# ADC_CLK.net
KiCad netlist of a schematic drawn in Altium Designer
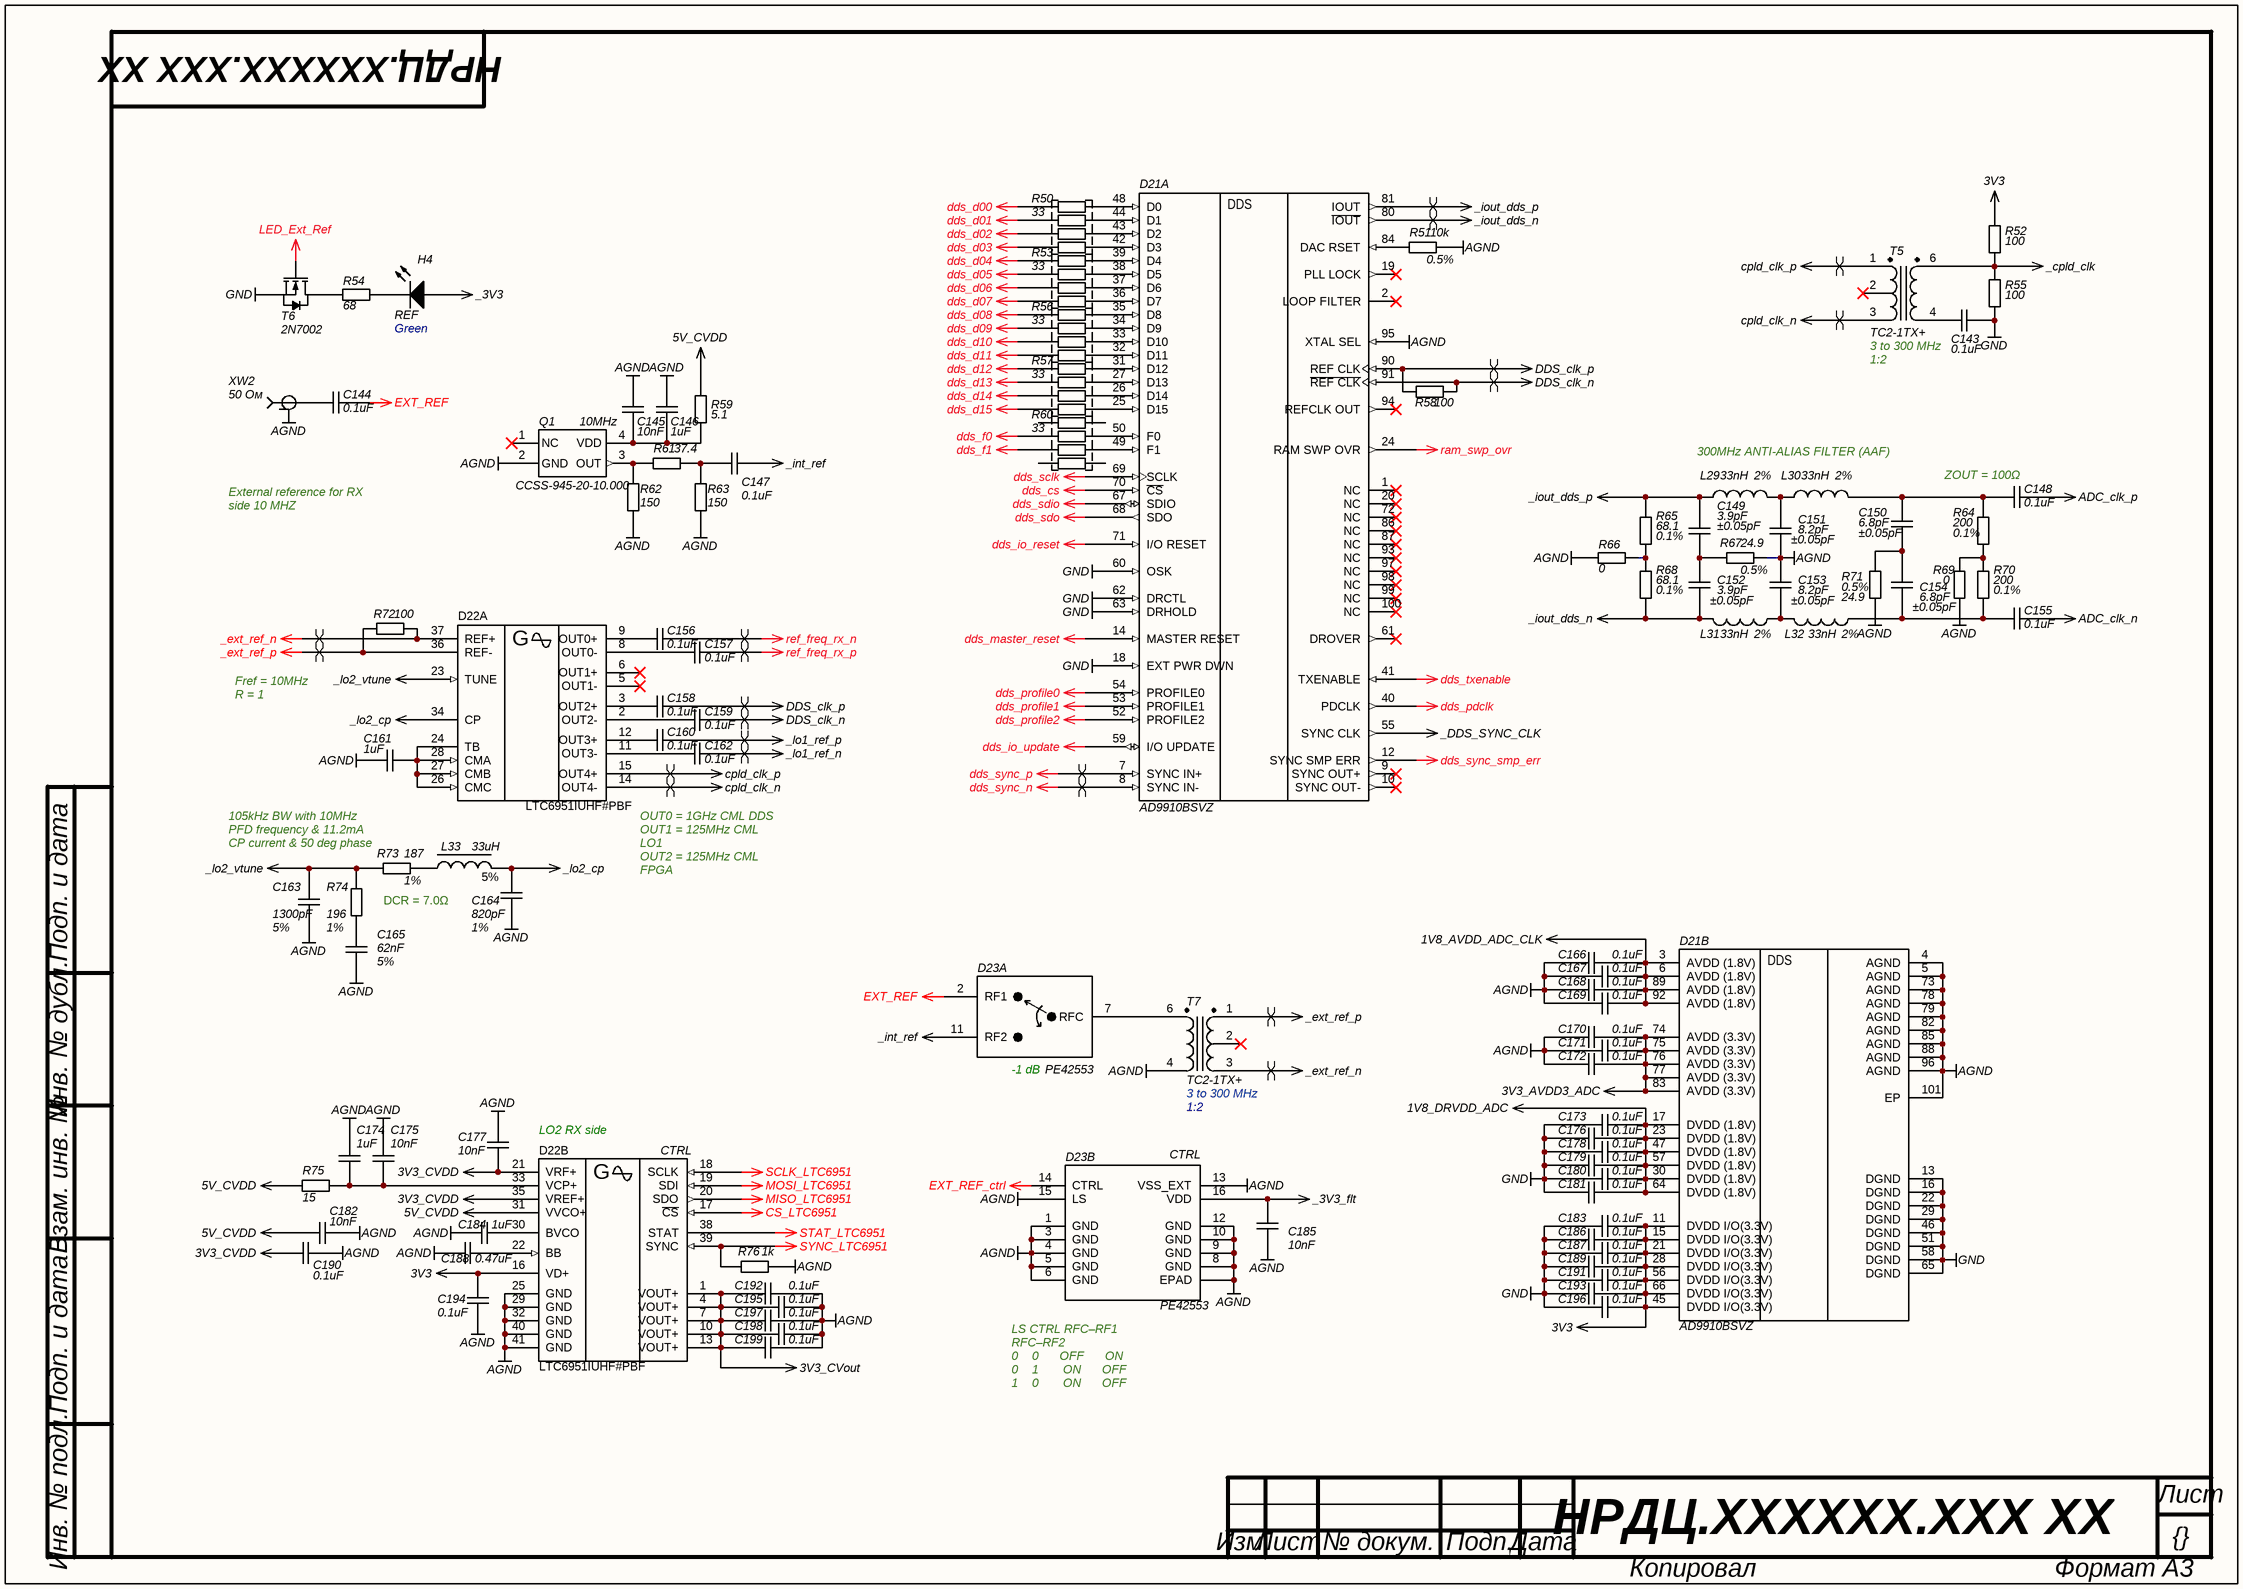
[diagram p0: ADC_CLK.SchDoc]

(export (version "E")
  (design (tool "Eeschema 10.0.6"))
  (components
    (comp (ref "C143")
      (value "0.1uF")
      (footprint "C0402")
      (description "SMD Capacitor")
      (fields (field (name "MANUFACTURER") "Murata") (field (name "TOLERANCE") "10%"))
      (libsource (lib "Kintex_SDR") (part "CAP"))
    )
    (comp (ref "C144")
      (value "0.1uF")
      (footprint "C0402")
      (description "SMD Capacitor")
      (fields (field (name "MANUFACTURER") "Murata") (field (name "TOLERANCE") "10%"))
      (libsource (lib "Kintex_SDR") (part "CAP"))
    )
    (comp (ref "C145")
      (value "10nF")
      (footprint "C0402")
      (description "SMD Capacitor")
      (fields (field (name "MANUFACTURER") "Murata") (field (name "TOLERANCE") "10%"))
      (libsource (lib "Kintex_SDR") (part "CAP"))
    )
    (comp (ref "C146")
      (value "1uF")
      (footprint "C0805")
      (description "SMD Capacitor")
      (fields (field (name "MANUFACTURER") "Murata") (field (name "TOLERANCE") "10%"))
      (libsource (lib "Kintex_SDR") (part "CAP"))
    )
    (comp (ref "C147")
      (value "0.1uF")
      (footprint "C0402")
      (description "SMD Capacitor")
      (fields (field (name "MANUFACTURER") "Murata") (field (name "TOLERANCE") "10%"))
      (libsource (lib "Kintex_SDR") (part "CAP"))
    )
    (comp (ref "C148")
      (value "0.1uF")
      (footprint "C0402")
      (description "SMD Capacitor")
      (fields (field (name "MANUFACTURER") "Murata") (field (name "TOLERANCE") "10%"))
      (libsource (lib "Kintex_SDR") (part "CAP"))
    )
    (comp (ref "C149")
      (value "3.9pF")
      (footprint "C0402")
      (description "SMD Capacitor")
      (fields
        (field (name "MANUFACTURER") "Murata")
        (field (name "TOLERANCE") "±0.05pF")
        (field (name "VOLTAGE") "50V")
      )
      (libsource (lib "Kintex_SDR") (part "CAP"))
    )
    (comp (ref "C150")
      (value "6.8pF")
      (footprint "C0402")
      (description "SMD Capacitor")
      (fields
        (field (name "MANUFACTURER") "Murata")
        (field (name "TOLERANCE") "±0.05pF")
        (field (name "VOLTAGE") "50V")
      )
      (libsource (lib "Kintex_SDR") (part "CAP"))
    )
    (comp (ref "C151")
      (value "8.2pF")
      (footprint "C0402")
      (description "SMD Capacitor")
      (fields
        (field (name "MANUFACTURER") "Murata")
        (field (name "TOLERANCE") "±0.05pF")
        (field (name "VOLTAGE") "50V")
      )
      (libsource (lib "Kintex_SDR") (part "CAP"))
    )
    (comp (ref "C152")
      (value "3.9pF")
      (footprint "C0402")
      (description "SMD Capacitor")
      (fields
        (field (name "MANUFACTURER") "Murata")
        (field (name "TOLERANCE") "±0.05pF")
        (field (name "VOLTAGE") "50V")
      )
      (libsource (lib "Kintex_SDR") (part "CAP"))
    )
    (comp (ref "C153")
      (value "8.2pF")
      (footprint "C0402")
      (description "SMD Capacitor")
      (fields
        (field (name "MANUFACTURER") "Murata")
        (field (name "TOLERANCE") "±0.05pF")
        (field (name "VOLTAGE") "50V")
      )
      (libsource (lib "Kintex_SDR") (part "CAP"))
    )
    (comp (ref "C154")
      (value "6.8pF")
      (footprint "C0402")
      (description "SMD Capacitor")
      (fields
        (field (name "MANUFACTURER") "Murata")
        (field (name "TOLERANCE") "±0.05pF")
        (field (name "VOLTAGE") "50V")
      )
      (libsource (lib "Kintex_SDR") (part "CAP"))
    )
    (comp (ref "C155")
      (value "0.1uF")
      (footprint "C0402")
      (description "SMD Capacitor")
      (fields (field (name "MANUFACTURER") "Murata") (field (name "TOLERANCE") "10%"))
      (libsource (lib "Kintex_SDR") (part "CAP"))
    )
    (comp (ref "C156")
      (value "0.1uF")
      (footprint "C0402")
      (description "SMD Capacitor")
      (fields (field (name "MANUFACTURER") "Murata") (field (name "TOLERANCE") "10%"))
      (libsource (lib "Kintex_SDR") (part "CAP"))
    )
    (comp (ref "C157")
      (value "0.1uF")
      (footprint "C0402")
      (description "SMD Capacitor")
      (fields (field (name "MANUFACTURER") "Murata") (field (name "TOLERANCE") "10%"))
      (libsource (lib "Kintex_SDR") (part "CAP"))
    )
    (comp (ref "C158")
      (value "0.1uF")
      (footprint "C0402")
      (description "SMD Capacitor")
      (fields (field (name "MANUFACTURER") "Murata") (field (name "TOLERANCE") "10%"))
      (libsource (lib "Kintex_SDR") (part "CAP"))
    )
    (comp (ref "C159")
      (value "0.1uF")
      (footprint "C0402")
      (description "SMD Capacitor")
      (fields (field (name "MANUFACTURER") "Murata") (field (name "TOLERANCE") "10%"))
      (libsource (lib "Kintex_SDR") (part "CAP"))
    )
    (comp (ref "C160")
      (value "0.1uF")
      (footprint "C0402")
      (description "SMD Capacitor")
      (fields (field (name "MANUFACTURER") "Murata") (field (name "TOLERANCE") "10%"))
      (libsource (lib "Kintex_SDR") (part "CAP"))
    )
    (comp (ref "C161")
      (value "1uF")
      (footprint "C0402")
      (description "SMD Capacitor")
      (fields (field (name "MANUFACTURER") "Murata") (field (name "TOLERANCE") "10%"))
      (libsource (lib "Kintex_SDR") (part "CAP"))
    )
    (comp (ref "C162")
      (value "0.1uF")
      (footprint "C0402")
      (description "SMD Capacitor")
      (fields (field (name "MANUFACTURER") "Murata") (field (name "TOLERANCE") "10%"))
      (libsource (lib "Kintex_SDR") (part "CAP"))
    )
    (comp (ref "C163")
      (value "1300pF")
      (footprint "C0603")
      (description "SMD Capacitor")
      (fields
        (field (name "MANUFACTURER") "Murata")
        (field (name "TOLERANCE") "5%")
        (field (name "VOLTAGE") "50V")
      )
      (libsource (lib "Kintex_SDR") (part "CAP"))
    )
    (comp (ref "C164")
      (value "820pF")
      (footprint "C0603")
      (description "SMD Capacitor")
      (fields
        (field (name "MANUFACTURER") "Murata")
        (field (name "TOLERANCE") "1%")
        (field (name "VOLTAGE") "100V")
      )
      (libsource (lib "Kintex_SDR") (part "CAP"))
    )
    (comp (ref "C165")
      (value "62nF")
      (footprint "C1206")
      (description "SMD Capacitor")
      (fields
        (field (name "MANUFACTURER") "Murata")
        (field (name "TOLERANCE") "5%")
        (field (name "VOLTAGE") "50V")
      )
      (libsource (lib "Kintex_SDR") (part "CAP"))
    )
    (comp (ref "C166")
      (value "0.1uF")
      (footprint "C0402")
      (description "SMD Capacitor")
      (fields (field (name "MANUFACTURER") "Murata") (field (name "TOLERANCE") "10%"))
      (libsource (lib "Kintex_SDR") (part "CAP"))
    )
    (comp (ref "C167")
      (value "0.1uF")
      (footprint "C0402")
      (description "SMD Capacitor")
      (fields (field (name "MANUFACTURER") "Murata") (field (name "TOLERANCE") "10%"))
      (libsource (lib "Kintex_SDR") (part "CAP"))
    )
    (comp (ref "C168")
      (value "0.1uF")
      (footprint "C0402")
      (description "SMD Capacitor")
      (fields (field (name "MANUFACTURER") "Murata") (field (name "TOLERANCE") "10%"))
      (libsource (lib "Kintex_SDR") (part "CAP"))
    )
    (comp (ref "C169")
      (value "0.1uF")
      (footprint "C0402")
      (description "SMD Capacitor")
      (fields (field (name "MANUFACTURER") "Murata") (field (name "TOLERANCE") "10%"))
      (libsource (lib "Kintex_SDR") (part "CAP"))
    )
    (comp (ref "C170")
      (value "0.1uF")
      (footprint "C0402")
      (description "SMD Capacitor")
      (fields (field (name "MANUFACTURER") "Murata") (field (name "TOLERANCE") "10%"))
      (libsource (lib "Kintex_SDR") (part "CAP"))
    )
    (comp (ref "C171")
      (value "0.1uF")
      (footprint "C0402")
      (description "SMD Capacitor")
      (fields (field (name "MANUFACTURER") "Murata") (field (name "TOLERANCE") "10%"))
      (libsource (lib "Kintex_SDR") (part "CAP"))
    )
    (comp (ref "C172")
      (value "0.1uF")
      (footprint "C0402")
      (description "SMD Capacitor")
      (fields (field (name "MANUFACTURER") "Murata") (field (name "TOLERANCE") "10%"))
      (libsource (lib "Kintex_SDR") (part "CAP"))
    )
    (comp (ref "C173")
      (value "0.1uF")
      (footprint "C0402")
      (description "SMD Capacitor")
      (fields (field (name "MANUFACTURER") "Murata") (field (name "TOLERANCE") "10%"))
      (libsource (lib "Kintex_SDR") (part "CAP"))
    )
    (comp (ref "C174")
      (value "1uF")
      (footprint "C0805")
      (description "SMD Capacitor")
      (fields (field (name "MANUFACTURER") "Murata") (field (name "TOLERANCE") "10%"))
      (libsource (lib "Kintex_SDR") (part "CAP"))
    )
    (comp (ref "C175")
      (value "10nF")
      (footprint "C0402")
      (description "SMD Capacitor")
      (fields (field (name "MANUFACTURER") "Murata") (field (name "TOLERANCE") "10%"))
      (libsource (lib "Kintex_SDR") (part "CAP"))
    )
    (comp (ref "C176")
      (value "0.1uF")
      (footprint "C0402")
      (description "SMD Capacitor")
      (fields (field (name "MANUFACTURER") "Murata") (field (name "TOLERANCE") "10%"))
      (libsource (lib "Kintex_SDR") (part "CAP"))
    )
    (comp (ref "C177")
      (value "10nF")
      (footprint "C0402")
      (description "SMD Capacitor")
      (fields (field (name "MANUFACTURER") "Murata") (field (name "TOLERANCE") "10%"))
      (libsource (lib "Kintex_SDR") (part "CAP"))
    )
    (comp (ref "C178")
      (value "0.1uF")
      (footprint "C0402")
      (description "SMD Capacitor")
      (fields (field (name "MANUFACTURER") "Murata") (field (name "TOLERANCE") "10%"))
      (libsource (lib "Kintex_SDR") (part "CAP"))
    )
    (comp (ref "C179")
      (value "0.1uF")
      (footprint "C0402")
      (description "SMD Capacitor")
      (fields (field (name "MANUFACTURER") "Murata") (field (name "TOLERANCE") "10%"))
      (libsource (lib "Kintex_SDR") (part "CAP"))
    )
    (comp (ref "C180")
      (value "0.1uF")
      (footprint "C0402")
      (description "SMD Capacitor")
      (fields (field (name "MANUFACTURER") "Murata") (field (name "TOLERANCE") "10%"))
      (libsource (lib "Kintex_SDR") (part "CAP"))
    )
    (comp (ref "C181")
      (value "0.1uF")
      (footprint "C0402")
      (description "SMD Capacitor")
      (fields (field (name "MANUFACTURER") "Murata") (field (name "TOLERANCE") "10%"))
      (libsource (lib "Kintex_SDR") (part "CAP"))
    )
    (comp (ref "C182")
      (value "10nF")
      (footprint "C0402")
      (description "SMD Capacitor")
      (fields (field (name "MANUFACTURER") "Murata") (field (name "TOLERANCE") "10%"))
      (libsource (lib "Kintex_SDR") (part "CAP"))
    )
    (comp (ref "C183")
      (value "0.1uF")
      (footprint "C0402")
      (description "SMD Capacitor")
      (fields (field (name "MANUFACTURER") "Murata") (field (name "TOLERANCE") "10%"))
      (libsource (lib "Kintex_SDR") (part "CAP"))
    )
    (comp (ref "C184")
      (value "1uF")
      (footprint "C0402")
      (description "SMD Capacitor")
      (fields (field (name "MANUFACTURER") "Murata") (field (name "TOLERANCE") "10%"))
      (libsource (lib "Kintex_SDR") (part "CAP"))
    )
    (comp (ref "C185")
      (value "10nF")
      (footprint "C0402")
      (description "SMD Capacitor")
      (fields (field (name "MANUFACTURER") "Murata") (field (name "TOLERANCE") "10%"))
      (libsource (lib "Kintex_SDR") (part "CAP"))
    )
    (comp (ref "C186")
      (value "0.1uF")
      (footprint "C0402")
      (description "SMD Capacitor")
      (fields (field (name "MANUFACTURER") "Murata") (field (name "TOLERANCE") "10%"))
      (libsource (lib "Kintex_SDR") (part "CAP"))
    )
    (comp (ref "C187")
      (value "0.1uF")
      (footprint "C0402")
      (description "SMD Capacitor")
      (fields (field (name "MANUFACTURER") "Murata") (field (name "TOLERANCE") "10%"))
      (libsource (lib "Kintex_SDR") (part "CAP"))
    )
    (comp (ref "C188")
      (value "0.47uF")
      (footprint "C0603")
      (description "SMD Capacitor")
      (fields (field (name "MANUFACTURER") "Murata") (field (name "TOLERANCE") "10%"))
      (libsource (lib "Kintex_SDR") (part "CAP"))
    )
    (comp (ref "C189")
      (value "0.1uF")
      (footprint "C0402")
      (description "SMD Capacitor")
      (fields (field (name "MANUFACTURER") "Murata") (field (name "TOLERANCE") "10%"))
      (libsource (lib "Kintex_SDR") (part "CAP"))
    )
    (comp (ref "C190")
      (value "0.1uF")
      (footprint "C0402")
      (description "SMD Capacitor")
      (fields (field (name "MANUFACTURER") "Murata") (field (name "TOLERANCE") "10%"))
      (libsource (lib "Kintex_SDR") (part "CAP"))
    )
    (comp (ref "C191")
      (value "0.1uF")
      (footprint "C0402")
      (description "SMD Capacitor")
      (fields (field (name "MANUFACTURER") "Murata") (field (name "TOLERANCE") "10%"))
      (libsource (lib "Kintex_SDR") (part "CAP"))
    )
    (comp (ref "C192")
      (value "0.1uF")
      (footprint "C0402")
      (description "SMD Capacitor")
      (fields (field (name "MANUFACTURER") "Murata") (field (name "TOLERANCE") "10%"))
      (libsource (lib "Kintex_SDR") (part "CAP"))
    )
    (comp (ref "C193")
      (value "0.1uF")
      (footprint "C0402")
      (description "SMD Capacitor")
      (fields (field (name "MANUFACTURER") "Murata") (field (name "TOLERANCE") "10%"))
      (libsource (lib "Kintex_SDR") (part "CAP"))
    )
    (comp (ref "C194")
      (value "0.1uF")
      (footprint "C0402")
      (description "SMD Capacitor")
      (fields (field (name "MANUFACTURER") "Murata") (field (name "TOLERANCE") "10%"))
      (libsource (lib "Kintex_SDR") (part "CAP"))
    )
    (comp (ref "C195")
      (value "0.1uF")
      (footprint "C0402")
      (description "SMD Capacitor")
      (fields (field (name "MANUFACTURER") "Murata") (field (name "TOLERANCE") "10%"))
      (libsource (lib "Kintex_SDR") (part "CAP"))
    )
    (comp (ref "C196")
      (value "0.1uF")
      (footprint "C0402")
      (description "SMD Capacitor")
      (fields (field (name "MANUFACTURER") "Murata") (field (name "TOLERANCE") "10%"))
      (libsource (lib "Kintex_SDR") (part "CAP"))
    )
    (comp (ref "C197")
      (value "0.1uF")
      (footprint "C0402")
      (description "SMD Capacitor")
      (fields (field (name "MANUFACTURER") "Murata") (field (name "TOLERANCE") "10%"))
      (libsource (lib "Kintex_SDR") (part "CAP"))
    )
    (comp (ref "C198")
      (value "0.1uF")
      (footprint "C0402")
      (description "SMD Capacitor")
      (fields (field (name "MANUFACTURER") "Murata") (field (name "TOLERANCE") "10%"))
      (libsource (lib "Kintex_SDR") (part "CAP"))
    )
    (comp (ref "C199")
      (value "0.1uF")
      (footprint "C0402")
      (description "SMD Capacitor")
      (fields (field (name "MANUFACTURER") "Murata") (field (name "TOLERANCE") "10%"))
      (libsource (lib "Kintex_SDR") (part "CAP"))
    )
    (comp (ref "D21")
      (value "AD9910BSVZ")
      (footprint "DBLib:Analog_Devices_SV-100-4_IPC_A")
      (description "1 GSPS, 14-Bit, 3.3 V CMOS\r\nDirect Digital Synthesizer")
      (libsource (lib "DBLib") (part "AD9910"))
    )
    (comp (ref "D22")
      (value "LTC6951IUHF#PBF")
      (footprint "DBLib:Analog_Devices_UHF-40-05-08-1951_IPC_A")
      (description "Ultralow Jitter\r\nMultioutput Clock Synthesizer\r\nwith Integrated VCO")
      (libsource (lib "") (part "LTC6951_1"))
    )
    (comp (ref "D23")
      (value "PE42553")
      (footprint "QFN-16")
      (description "HaRPTM technology-enhanced absorptive SPDT")
      (fields (field (name "MANUFACTURER") "Peregrine Technical Solutions"))
      (libsource (lib "") (part "PE42553_1"))
    )
    (comp (ref "H4")
      (value "REF")
      (footprint "LED")
      (description "CHIP LED LAMP")
      (fields (field (name "MANUFACTURER") "Kingbright") (field (name "COLOR") "Green"))
      (libsource (lib "DBLib") (part "LED"))
    )
    (comp (ref "L29")
      (value "33nH")
      (footprint "DBLib:L0603_HP")
      (description "Chip SMD Inductor")
      (fields
        (field (name "MANUFACTURER") "Coilcraft")
        (field (name "TOLERANCE") "2%")
        (field (name "Comment") "Inductor RF")
      )
      (libsource (lib "DBLib") (part "Inductor RF"))
    )
    (comp (ref "L30")
      (value "33nH")
      (footprint "DBLib:L0603_HP")
      (description "Chip SMD Inductor")
      (fields
        (field (name "MANUFACTURER") "Coilcraft")
        (field (name "TOLERANCE") "2%")
        (field (name "Comment") "Inductor RF")
      )
      (libsource (lib "DBLib") (part "Inductor RF"))
    )
    (comp (ref "L31")
      (value "33nH")
      (footprint "DBLib:L0603_HP")
      (description "Chip SMD Inductor")
      (fields
        (field (name "MANUFACTURER") "Coilcraft")
        (field (name "TOLERANCE") "2%")
        (field (name "Comment") "Inductor RF")
      )
      (libsource (lib "") (part "Inductor RF_1"))
    )
    (comp (ref "L32")
      (value "33nH")
      (footprint "DBLib:L0603_HP")
      (description "Chip SMD Inductor")
      (fields
        (field (name "MANUFACTURER") "Coilcraft")
        (field (name "TOLERANCE") "2%")
        (field (name "Comment") "Inductor RF")
      )
      (libsource (lib "") (part "Inductor RF_1"))
    )
    (comp (ref "L33")
      (value "33uH")
      (footprint "DBLib:L1008_LS")
      (description "Chip SMD Inductor")
      (fields
        (field (name "MANUFACTURER") "Coilcraft")
        (field (name "TOLERANCE") "5%")
        (field (name "Comment") "Inductor")
      )
      (libsource (lib "DBLib") (part "Inductor"))
    )
    (comp (ref "Q1")
      (value "CCSS-945-20-10.000")
      (footprint "DBLib:CVCSO-914")
      (description "Ultra Low Noise\r\nSineWave Clock Oscillator")
      (fields (field (name "VOLTAGE") "5.0V") (field (name "FREQUENCY") "10MHz"))
      (libsource (lib "DBLib") (part "CCSS-945"))
    )
    (comp (ref "R50")
      (value "33")
      (footprint "EXN8V")
      (description "Chip Resistor Array")
      (fields (field (name "TOLERANCE") "5%") (field (name "MANUFACTURER") "Panasonic"))
      (libsource (lib "Kintex_SDR") (part "RES 4x0402"))
    )
    (comp (ref "R51")
      (value "10k")
      (footprint "R0402")
      (description "SMD Resistor")
      (fields
        (field (name "POWER") "0.063 Wt")
        (field (name "TOLERANCE") "0.5%")
        (field (name "MANUFACTURER") "Panasonic Electronic Components")
      )
      (libsource (lib "") (part "RES_1"))
    )
    (comp (ref "R52")
      (value "100")
      (footprint "R0402")
      (description "SMD Resistor")
      (fields (field (name "POWER") "0.062 Wt") (field (name "TOLERANCE") "5%"))
      (libsource (lib "") (part "RES_3"))
    )
    (comp (ref "R53")
      (value "33")
      (footprint "EXN8V")
      (description "Chip Resistor Array")
      (fields (field (name "TOLERANCE") "5%") (field (name "MANUFACTURER") "Panasonic"))
      (libsource (lib "Kintex_SDR") (part "RES 4x0402"))
    )
    (comp (ref "R54")
      (value "68")
      (footprint "R0402")
      (description "SMD Resistor")
      (fields (field (name "POWER") "0.062 Wt") (field (name "TOLERANCE") "5%"))
      (libsource (lib "") (part "RES_1"))
    )
    (comp (ref "R55")
      (value "100")
      (footprint "R0402")
      (description "SMD Resistor")
      (fields (field (name "POWER") "0.062 Wt") (field (name "TOLERANCE") "5%"))
      (libsource (lib "") (part "RES_3"))
    )
    (comp (ref "R56")
      (value "33")
      (footprint "EXN8V")
      (description "Chip Resistor Array")
      (fields (field (name "TOLERANCE") "5%") (field (name "MANUFACTURER") "Panasonic"))
      (libsource (lib "Kintex_SDR") (part "RES 4x0402"))
    )
    (comp (ref "R57")
      (value "33")
      (footprint "EXN8V")
      (description "Chip Resistor Array")
      (fields (field (name "TOLERANCE") "5%") (field (name "MANUFACTURER") "Panasonic"))
      (libsource (lib "Kintex_SDR") (part "RES 4x0402"))
    )
    (comp (ref "R58")
      (value "100")
      (footprint "R0402")
      (description "SMD Resistor")
      (fields (field (name "POWER") "0.062 Wt") (field (name "TOLERANCE") "5%"))
      (libsource (lib "") (part "RES_2"))
    )
    (comp (ref "R59")
      (value "5.1")
      (footprint "R0603")
      (description "SMD Resistor")
      (fields (field (name "POWER") "0.1 Wt") (field (name "TOLERANCE") "5%"))
      (libsource (lib "Kintex_SDR") (part "RES"))
    )
    (comp (ref "R60")
      (value "33")
      (footprint "EXN8V")
      (description "Chip Resistor Array")
      (fields (field (name "TOLERANCE") "5%") (field (name "MANUFACTURER") "Panasonic"))
      (libsource (lib "Kintex_SDR") (part "RES 4x0402"))
    )
    (comp (ref "R61")
      (value "37.4")
      (footprint "R0402")
      (description "SMD Resistor")
      (fields (field (name "POWER") "0.062 Wt") (field (name "TOLERANCE") "5%"))
      (libsource (lib "") (part "RES_1"))
    )
    (comp (ref "R62")
      (value "150")
      (footprint "R0402")
      (description "SMD Resistor")
      (fields (field (name "POWER") "0.062 Wt") (field (name "TOLERANCE") "1%"))
      (libsource (lib "") (part "RES_1"))
    )
    (comp (ref "R63")
      (value "150")
      (footprint "R0402")
      (description "SMD Resistor")
      (fields (field (name "POWER") "0.062 Wt") (field (name "TOLERANCE") "1%"))
      (libsource (lib "") (part "RES_1"))
    )
    (comp (ref "R64")
      (value "200")
      (footprint "R0402")
      (description "SMD Resistor")
      (fields
        (field (name "POWER") "0.063 Wt")
        (field (name "TOLERANCE") "0.1%")
        (field (name "MANUFACTURER") "Panasonic Electronic Components")
      )
      (libsource (lib "") (part "RES_2"))
    )
    (comp (ref "R65")
      (value "68.1")
      (footprint "R0402")
      (description "SMD Resistor")
      (fields
        (field (name "POWER") "0.063 Wt")
        (field (name "TOLERANCE") "0.1%")
        (field (name "MANUFACTURER") "Panasonic Electronic Components")
      )
      (libsource (lib "") (part "RES_2"))
    )
    (comp (ref "R66")
      (value "0")
      (footprint "R0402")
      (description "SMD Resistor")
      (fields (field (name "POWER") "0.1 Wt") (field (name "TOLERANCE") "1%"))
      (libsource (lib "Kintex_SDR") (part "RES"))
    )
    (comp (ref "R67")
      (value "24.9")
      (footprint "R0402")
      (description "SMD Resistor")
      (fields
        (field (name "POWER") "0.063 Wt")
        (field (name "TOLERANCE") "0.5%")
        (field (name "MANUFACTURER") "Panasonic Electronic Components")
      )
      (libsource (lib "Kintex_SDR") (part "RES"))
    )
    (comp (ref "R68")
      (value "68.1")
      (footprint "R0402")
      (description "SMD Resistor")
      (fields
        (field (name "POWER") "0.063 Wt")
        (field (name "TOLERANCE") "0.1%")
        (field (name "MANUFACTURER") "Panasonic Electronic Components")
      )
      (libsource (lib "") (part "RES_2"))
    )
    (comp (ref "R69")
      (value "0")
      (footprint "R0402")
      (description "SMD Resistor")
      (fields (field (name "POWER") "0.1 Wt") (field (name "TOLERANCE") "1%"))
      (libsource (lib "") (part "RES_2"))
    )
    (comp (ref "R70")
      (value "200")
      (footprint "R0402")
      (description "SMD Resistor")
      (fields
        (field (name "POWER") "0.063 Wt")
        (field (name "TOLERANCE") "0.1%")
        (field (name "MANUFACTURER") "Panasonic Electronic Components")
      )
      (libsource (lib "") (part "RES_2"))
    )
    (comp (ref "R71")
      (value "24.9")
      (footprint "R0402")
      (description "SMD Resistor")
      (fields
        (field (name "POWER") "0.063 Wt")
        (field (name "TOLERANCE") "0.5%")
        (field (name "MANUFACTURER") "Panasonic Electronic Components")
      )
      (libsource (lib "") (part "RES_2"))
    )
    (comp (ref "R72")
      (value "100")
      (footprint "R0402")
      (description "SMD Resistor")
      (fields (field (name "POWER") "0.062 Wt") (field (name "TOLERANCE") "5%"))
      (libsource (lib "Kintex_SDR") (part "RES"))
    )
    (comp (ref "R73")
      (value "187")
      (footprint "R0402")
      (description "SMD Resistor")
      (fields
        (field (name "POWER") "0.2 Wt")
        (field (name "TOLERANCE") "1%")
        (field (name "MANUFACTURER") "Panasonic Electronic Components")
      )
      (libsource (lib "") (part "RES_1"))
    )
    (comp (ref "R74")
      (value "196")
      (footprint "R0402")
      (description "SMD Resistor")
      (fields
        (field (name "POWER") "0.2 Wt")
        (field (name "TOLERANCE") "1%")
        (field (name "MANUFACTURER") "Panasonic Electronic Components")
      )
      (libsource (lib "") (part "RES_2"))
    )
    (comp (ref "R75")
      (value "15")
      (footprint "R0603")
      (description "SMD Resistor")
      (fields (field (name "POWER") "0.1 Wt") (field (name "TOLERANCE") "1%"))
      (libsource (lib "") (part "RES_1"))
    )
    (comp (ref "R76")
      (value "1k")
      (footprint "R0402")
      (description "SMD Resistor")
      (fields (field (name "POWER") "0.062 Wt") (field (name "TOLERANCE") "5%"))
      (libsource (lib "") (part "RES_2"))
    )
    (comp (ref "T5")
      (value "TC2-1TX+")
      (footprint "DBLib:AT1521")
      (description "RF Transformer")
      (fields
        (field (name "MANUFACTURER") "Mini-Circuits")
        (field (name "FREQUENCY") "3 to 300 MHz")
        (field (name "RATIO") "1:2")
      )
      (libsource (lib "") (part "TC2-1TX+_1"))
    )
    (comp (ref "T6")
      (value "2N7002")
      (footprint "SOT-23")
      (description "N-Channel MOSFET 2N7002")
      (fields (field (name "VOLTAGE") "60V"))
      (libsource (lib "Kintex_SDR") (part "2N7002"))
    )
    (comp (ref "T7")
      (value "TC2-1TX+")
      (footprint "DBLib:AT1521")
      (description "RF Transformer")
      (fields
        (field (name "MANUFACTURER") "Mini-Circuits")
        (field (name "FREQUENCY") "3 to 300 MHz")
        (field (name "RATIO") "1:2")
      )
      (libsource (lib "DBLib") (part "TC2-1TX+"))
    )
    (comp (ref "XW2")
      (value "50 Ом")
      (footprint "MOLEX SD-73251-135 (Gold)")
      (description "50 Ohms, SMA Jack, Vertica")
      (fields (field (name "MANUFACTURER") "Molex"))
      (libsource (lib "DBLib") (part "RF Connector"))
    )
  )
  (nets
    (net (code "1") (name "1V8_AVDD_ADC_CLK") (class "Default")
      (node (ref "C166") (pin "2") (pinfunction "2_2") (pintype "passive"))
      (node (ref "C167") (pin "2") (pinfunction "2_2") (pintype "passive"))
      (node (ref "C168") (pin "2") (pinfunction "2_2") (pintype "passive"))
      (node (ref "C169") (pin "2") (pinfunction "2_2") (pintype "passive"))
      (node (ref "D21") (pin "3") (pinfunction "AVDD_(1.8V)_3") (pintype "power_in"))
      (node (ref "D21") (pin "6") (pinfunction "AVDD_(1.8V)_6") (pintype "power_in"))
      (node (ref "D21") (pin "89") (pinfunction "AVDD_(1.8V)_89") (pintype "power_in"))
      (node (ref "D21") (pin "92") (pinfunction "AVDD_(1.8V)_92") (pintype "power_in"))
    )
    (net (code "2") (name "1V8_DRVDD_ADC") (class "Default")
      (node (ref "C173") (pin "2") (pinfunction "2_2") (pintype "passive"))
      (node (ref "C176") (pin "2") (pinfunction "2_2") (pintype "passive"))
      (node (ref "C178") (pin "2") (pinfunction "2_2") (pintype "passive"))
      (node (ref "C179") (pin "2") (pinfunction "2_2") (pintype "passive"))
      (node (ref "C180") (pin "2") (pinfunction "2_2") (pintype "passive"))
      (node (ref "C181") (pin "2") (pinfunction "2_2") (pintype "passive"))
      (node (ref "D21") (pin "17") (pinfunction "DVDD_(1.8V)_17") (pintype "power_in"))
      (node (ref "D21") (pin "23") (pinfunction "DVDD_(1.8V)_23") (pintype "power_in"))
      (node (ref "D21") (pin "30") (pinfunction "DVDD_(1.8V)_30") (pintype "power_in"))
      (node (ref "D21") (pin "47") (pinfunction "DVDD_(1.8V)_47") (pintype "power_in"))
      (node (ref "D21") (pin "57") (pinfunction "DVDD_(1.8V)_57") (pintype "power_in"))
      (node (ref "D21") (pin "64") (pinfunction "DVDD_(1.8V)_64") (pintype "power_in"))
    )
    (net (code "3") (name "3V3") (class "Default")
      (node (ref "C183") (pin "2") (pinfunction "2_2") (pintype "passive"))
      (node (ref "C186") (pin "2") (pinfunction "2_2") (pintype "passive"))
      (node (ref "C187") (pin "2") (pinfunction "2_2") (pintype "passive"))
      (node (ref "C189") (pin "2") (pinfunction "2_2") (pintype "passive"))
      (node (ref "C191") (pin "2") (pinfunction "2_2") (pintype "passive"))
      (node (ref "C193") (pin "2") (pinfunction "2_2") (pintype "passive"))
      (node (ref "C194") (pin "2") (pinfunction "2_2") (pintype "passive"))
      (node (ref "C196") (pin "2") (pinfunction "2_2") (pintype "passive"))
      (node (ref "D21") (pin "11") (pinfunction "DVDD_I/O(3.3V)_11") (pintype "power_in"))
      (node (ref "D21") (pin "15") (pinfunction "DVDD_I/O(3.3V)_15") (pintype "power_in"))
      (node (ref "D21") (pin "21") (pinfunction "DVDD_I/O(3.3V)_21") (pintype "power_in"))
      (node (ref "D21") (pin "28") (pinfunction "DVDD_I/O(3.3V)_28") (pintype "power_in"))
      (node (ref "D21") (pin "45") (pinfunction "DVDD_I/O(3.3V)_45") (pintype "power_in"))
      (node (ref "D21") (pin "56") (pinfunction "DVDD_I/O(3.3V)_56") (pintype "power_in"))
      (node (ref "D21") (pin "66") (pinfunction "DVDD_I/O(3.3V)_66") (pintype "power_in"))
      (node (ref "D22") (pin "16") (pinfunction "VD+_16") (pintype "power_in"))
      (node (ref "R52") (pin "2") (pinfunction "2_2") (pintype "passive"))
    )
    (net (code "4") (name "3V3_AVDD3_ADC") (class "Default")
      (node (ref "C170") (pin "2") (pinfunction "2_2") (pintype "passive"))
      (node (ref "C171") (pin "2") (pinfunction "2_2") (pintype "passive"))
      (node (ref "C172") (pin "2") (pinfunction "2_2") (pintype "passive"))
      (node (ref "D21") (pin "74") (pinfunction "AVDD_(3.3V)_74") (pintype "power_in"))
      (node (ref "D21") (pin "75") (pinfunction "AVDD_(3.3V)_75") (pintype "power_in"))
      (node (ref "D21") (pin "76") (pinfunction "AVDD_(3.3V)_76") (pintype "power_in"))
      (node (ref "D21") (pin "77") (pinfunction "AVDD_(3.3V)_77") (pintype "power_in"))
      (node (ref "D21") (pin "83") (pinfunction "AVDD_(3.3V)_83") (pintype "power_in"))
    )
    (net (code "5") (name "3V3_CVDD") (class "Default")
      (node (ref "C177") (pin "2") (pinfunction "2_2") (pintype "passive"))
      (node (ref "C190") (pin "2") (pinfunction "2_2") (pintype "passive"))
      (node (ref "D22") (pin "21") (pinfunction "VRF+_21") (pintype "passive"))
      (node (ref "D22") (pin "35") (pinfunction "VREF+_35") (pintype "power_in"))
    )
    (net (code "6") (name "3V3_CVout") (class "Default")
      (node (ref "C192") (pin "1") (pinfunction "1_1") (pintype "passive"))
      (node (ref "C195") (pin "1") (pinfunction "1_1") (pintype "passive"))
      (node (ref "C197") (pin "1") (pinfunction "1_1") (pintype "passive"))
      (node (ref "C198") (pin "1") (pinfunction "1_1") (pintype "passive"))
      (node (ref "C199") (pin "1") (pinfunction "1_1") (pintype "passive"))
      (node (ref "D22") (pin "1") (pinfunction "VOUT+_1") (pintype "passive"))
      (node (ref "D22") (pin "10") (pinfunction "VOUT+_10") (pintype "passive"))
      (node (ref "D22") (pin "13") (pinfunction "VOUT+_13") (pintype "passive"))
      (node (ref "D22") (pin "4") (pinfunction "VOUT+_4") (pintype "passive"))
      (node (ref "D22") (pin "7") (pinfunction "VOUT+_7") (pintype "passive"))
    )
    (net (code "7") (name "5V_CVDD") (class "Default")
      (node (ref "C182") (pin "1") (pinfunction "1_1") (pintype "passive"))
      (node (ref "D22") (pin "31") (pinfunction "VVCO+_31") (pintype "power_in"))
      (node (ref "R59") (pin "2") (pinfunction "2_2") (pintype "passive"))
      (node (ref "R75") (pin "2") (pinfunction "2_2") (pintype "passive"))
    )
    (net (code "8") (name "ADC_clk_n") (class "Default")
      (node (ref "C155") (pin "1") (pinfunction "1_1") (pintype "passive"))
    )
    (net (code "9") (name "ADC_clk_p") (class "Default")
      (node (ref "C148") (pin "1") (pinfunction "1_1") (pintype "passive"))
    )
    (net (code "10") (name "AGND") (class "Default")
      (node (ref "C145") (pin "1") (pinfunction "1_1") (pintype "passive"))
      (node (ref "C146") (pin "1") (pinfunction "1_1") (pintype "passive"))
      (node (ref "C151") (pin "2") (pinfunction "2_2") (pintype "passive"))
      (node (ref "C153") (pin "1") (pinfunction "1_1") (pintype "passive"))
      (node (ref "C161") (pin "1") (pinfunction "1_1") (pintype "passive"))
      (node (ref "C163") (pin "1") (pinfunction "1_1") (pintype "passive"))
      (node (ref "C164") (pin "1") (pinfunction "1_1") (pintype "passive"))
      (node (ref "C165") (pin "1") (pinfunction "1_1") (pintype "passive"))
      (node (ref "C166") (pin "1") (pinfunction "1_1") (pintype "passive"))
      (node (ref "C167") (pin "1") (pinfunction "1_1") (pintype "passive"))
      (node (ref "C168") (pin "1") (pinfunction "1_1") (pintype "passive"))
      (node (ref "C169") (pin "1") (pinfunction "1_1") (pintype "passive"))
      (node (ref "C170") (pin "1") (pinfunction "1_1") (pintype "passive"))
      (node (ref "C171") (pin "1") (pinfunction "1_1") (pintype "passive"))
      (node (ref "C172") (pin "1") (pinfunction "1_1") (pintype "passive"))
      (node (ref "C174") (pin "1") (pinfunction "1_1") (pintype "passive"))
      (node (ref "C175") (pin "1") (pinfunction "1_1") (pintype "passive"))
      (node (ref "C177") (pin "1") (pinfunction "1_1") (pintype "passive"))
      (node (ref "C182") (pin "2") (pinfunction "2_2") (pintype "passive"))
      (node (ref "C184") (pin "1") (pinfunction "1_1") (pintype "passive"))
      (node (ref "C185") (pin "2") (pinfunction "2_2") (pintype "passive"))
      (node (ref "C188") (pin "2") (pinfunction "2_2") (pintype "passive"))
      (node (ref "C190") (pin "1") (pinfunction "1_1") (pintype "passive"))
      (node (ref "C192") (pin "2") (pinfunction "2_2") (pintype "passive"))
      (node (ref "C194") (pin "1") (pinfunction "1_1") (pintype "passive"))
      (node (ref "C195") (pin "2") (pinfunction "2_2") (pintype "passive"))
      (node (ref "C197") (pin "2") (pinfunction "2_2") (pintype "passive"))
      (node (ref "C198") (pin "2") (pinfunction "2_2") (pintype "passive"))
      (node (ref "C199") (pin "2") (pinfunction "2_2") (pintype "passive"))
      (node (ref "D21") (pin "101") (pinfunction "EP_101") (pintype "power_in"))
      (node (ref "D21") (pin "4") (pinfunction "AGND_4") (pintype "power_in"))
      (node (ref "D21") (pin "5") (pinfunction "AGND_5") (pintype "power_in"))
      (node (ref "D21") (pin "73") (pinfunction "AGND_73") (pintype "power_in"))
      (node (ref "D21") (pin "78") (pinfunction "AGND_78") (pintype "power_in"))
      (node (ref "D21") (pin "79") (pinfunction "AGND_79") (pintype "power_in"))
      (node (ref "D21") (pin "82") (pinfunction "AGND_82") (pintype "power_in"))
      (node (ref "D21") (pin "85") (pinfunction "AGND_85") (pintype "power_in"))
      (node (ref "D21") (pin "88") (pinfunction "AGND_88") (pintype "power_in"))
      (node (ref "D21") (pin "95") (pinfunction "XTAL_SEL_95") (pintype "input"))
      (node (ref "D21") (pin "96") (pinfunction "AGND_96") (pintype "power_in"))
      (node (ref "D22") (pin "25") (pinfunction "GND_25") (pintype "power_in"))
      (node (ref "D22") (pin "29") (pinfunction "GND_29") (pintype "power_in"))
      (node (ref "D22") (pin "32") (pinfunction "GND_32") (pintype "power_in"))
      (node (ref "D22") (pin "40") (pinfunction "GND_40") (pintype "power_in"))
      (node (ref "D22") (pin "41") (pinfunction "GND_41") (pintype "power_in"))
      (node (ref "D23") (pin "1") (pinfunction "GND_1") (pintype "passive"))
      (node (ref "D23") (pin "10") (pinfunction "GND_10") (pintype "passive"))
      (node (ref "D23") (pin "12") (pinfunction "GND_12") (pintype "passive"))
      (node (ref "D23") (pin "13") (pinfunction "VSS_EXT_13") (pintype "passive"))
      (node (ref "D23") (pin "15") (pinfunction "LS_15") (pintype "passive"))
      (node (ref "D23") (pin "17") (pinfunction "EPAD_17") (pintype "passive"))
      (node (ref "D23") (pin "3") (pinfunction "GND_3") (pintype "passive"))
      (node (ref "D23") (pin "4") (pinfunction "GND_4") (pintype "passive"))
      (node (ref "D23") (pin "5") (pinfunction "GND_5") (pintype "passive"))
      (node (ref "D23") (pin "6") (pinfunction "GND_6") (pintype "passive"))
      (node (ref "D23") (pin "8") (pinfunction "GND_8") (pintype "passive"))
      (node (ref "D23") (pin "9") (pinfunction "GND_9") (pintype "passive"))
      (node (ref "Q1") (pin "2") (pinfunction "GND_2") (pintype "passive"))
      (node (ref "R51") (pin "1") (pinfunction "1_1") (pintype "passive"))
      (node (ref "R62") (pin "2") (pinfunction "2_2") (pintype "passive"))
      (node (ref "R63") (pin "2") (pinfunction "2_2") (pintype "passive"))
      (node (ref "R66") (pin "1") (pinfunction "1_1") (pintype "passive"))
      (node (ref "R67") (pin "2") (pinfunction "2_2") (pintype "passive"))
      (node (ref "R69") (pin "2") (pinfunction "2_2") (pintype "passive"))
      (node (ref "R71") (pin "2") (pinfunction "2_2") (pintype "passive"))
      (node (ref "R76") (pin "1") (pinfunction "1_1") (pintype "passive"))
      (node (ref "T7") (pin "4") (pinfunction "4_4") (pintype "passive"))
      (node (ref "XW2") (pin "G") (pinfunction "GND_G") (pintype "passive"))
    )
    (net (code "11") (name "CS_LTC6951") (class "Default")
      (node (ref "D22") (pin "17") (pinfunction "~{CS}_17") (pintype "input"))
    )
    (net (code "12") (name "DDS_clk_n") (class "Default")
      (node (ref "C159") (pin "1") (pinfunction "1_1") (pintype "passive"))
      (node (ref "D21") (pin "91") (pinfunction "~{REF_CLK}_91") (pintype "input"))
      (node (ref "R58") (pin "1") (pinfunction "1_1") (pintype "passive"))
    )
    (net (code "13") (name "DDS_clk_p") (class "Default")
      (node (ref "C158") (pin "1") (pinfunction "1_1") (pintype "passive"))
      (node (ref "D21") (pin "90") (pinfunction "REF_CLK_90") (pintype "input"))
      (node (ref "R58") (pin "2") (pinfunction "2_2") (pintype "passive"))
    )
    (net (code "14") (name "EXT_REF") (class "Default")
      (node (ref "C144") (pin "1") (pinfunction "1_1") (pintype "passive"))
      (node (ref "D23") (pin "2") (pinfunction "RF1_2") (pintype "passive"))
    )
    (net (code "15") (name "EXT_REF_ctrl") (class "Default")
      (node (ref "D23") (pin "14") (pinfunction "CTRL_14") (pintype "passive"))
    )
    (net (code "16") (name "GND") (class "Default")
      (node (ref "C143") (pin "1") (pinfunction "1_1") (pintype "passive"))
      (node (ref "C173") (pin "1") (pinfunction "1_1") (pintype "passive"))
      (node (ref "C176") (pin "1") (pinfunction "1_1") (pintype "passive"))
      (node (ref "C178") (pin "1") (pinfunction "1_1") (pintype "passive"))
      (node (ref "C179") (pin "1") (pinfunction "1_1") (pintype "passive"))
      (node (ref "C180") (pin "1") (pinfunction "1_1") (pintype "passive"))
      (node (ref "C181") (pin "1") (pinfunction "1_1") (pintype "passive"))
      (node (ref "C183") (pin "1") (pinfunction "1_1") (pintype "passive"))
      (node (ref "C186") (pin "1") (pinfunction "1_1") (pintype "passive"))
      (node (ref "C187") (pin "1") (pinfunction "1_1") (pintype "passive"))
      (node (ref "C189") (pin "1") (pinfunction "1_1") (pintype "passive"))
      (node (ref "C191") (pin "1") (pinfunction "1_1") (pintype "passive"))
      (node (ref "C193") (pin "1") (pinfunction "1_1") (pintype "passive"))
      (node (ref "C196") (pin "1") (pinfunction "1_1") (pintype "passive"))
      (node (ref "D21") (pin "13") (pinfunction "DGND_13") (pintype "power_in"))
      (node (ref "D21") (pin "16") (pinfunction "DGND_16") (pintype "power_in"))
      (node (ref "D21") (pin "18") (pinfunction "EXT_PWR_DWN_18") (pintype "input"))
      (node (ref "D21") (pin "22") (pinfunction "DGND_22") (pintype "power_in"))
      (node (ref "D21") (pin "29") (pinfunction "DGND_29") (pintype "power_in"))
      (node (ref "D21") (pin "46") (pinfunction "DGND_46") (pintype "power_in"))
      (node (ref "D21") (pin "51") (pinfunction "DGND_51") (pintype "power_in"))
      (node (ref "D21") (pin "58") (pinfunction "DGND_58") (pintype "power_in"))
      (node (ref "D21") (pin "60") (pinfunction "OSK_60") (pintype "input"))
      (node (ref "D21") (pin "62") (pinfunction "DRCTL_62") (pintype "input"))
      (node (ref "D21") (pin "63") (pinfunction "DRHOLD_63") (pintype "input"))
      (node (ref "D21") (pin "65") (pinfunction "DGND_65") (pintype "power_in"))
      (node (ref "R55") (pin "1") (pinfunction "1_1") (pintype "passive"))
      (node (ref "T6") (pin "2") (pinfunction "S_2") (pintype "passive"))
    )
    (net (code "17") (name "LED_Ext_Ref") (class "Default")
      (node (ref "T6") (pin "1") (pinfunction "G_1") (pintype "passive"))
    )
    (net (code "18") (name "MISO_LTC6951") (class "Default")
      (node (ref "D22") (pin "20") (pinfunction "SDO_20") (pintype "output"))
    )
    (net (code "19") (name "MOSI_LTC6951") (class "Default")
      (node (ref "D22") (pin "19") (pinfunction "SDI_19") (pintype "input"))
    )
    (net (code "20") (name "Net-(C143-Pad2)") (class "Default")
      (node (ref "C143") (pin "2") (pinfunction "2_2") (pintype "passive"))
      (node (ref "T5") (pin "4") (pinfunction "4_4") (pintype "passive"))
    )
    (net (code "21") (name "Net-(C147-Pad2)") (class "Default")
      (node (ref "C147") (pin "2") (pinfunction "2_2") (pintype "passive"))
      (node (ref "R61") (pin "1") (pinfunction "1_1") (pintype "passive"))
      (node (ref "R63") (pin "1") (pinfunction "1_1") (pintype "passive"))
    )
    (net (code "22") (name "Net-(C148-Pad2)") (class "Default")
      (node (ref "C148") (pin "2") (pinfunction "2_2") (pintype "passive"))
      (node (ref "C150") (pin "1") (pinfunction "1_1") (pintype "passive"))
      (node (ref "L30") (pin "2") (pinfunction "2_2") (pintype "passive"))
      (node (ref "R64") (pin "1") (pinfunction "1_1") (pintype "passive"))
    )
    (net (code "23") (name "Net-(C149-Pad2)") (class "Default")
      (node (ref "C149") (pin "2") (pinfunction "2_2") (pintype "passive"))
      (node (ref "C152") (pin "1") (pinfunction "1_1") (pintype "passive"))
      (node (ref "R67") (pin "1") (pinfunction "1_1") (pintype "passive"))
    )
    (net (code "24") (name "Net-(C150-Pad2)") (class "Default")
      (node (ref "C150") (pin "2") (pinfunction "2_2") (pintype "passive"))
      (node (ref "C154") (pin "1") (pinfunction "1_1") (pintype "passive"))
      (node (ref "R71") (pin "1") (pinfunction "1_1") (pintype "passive"))
    )
    (net (code "25") (name "Net-(C151-Pad1)") (class "Default")
      (node (ref "C151") (pin "1") (pinfunction "1_1") (pintype "passive"))
      (node (ref "L29") (pin "2") (pinfunction "2_2") (pintype "passive"))
      (node (ref "L30") (pin "1") (pinfunction "1_1") (pintype "passive"))
    )
    (net (code "26") (name "Net-(C153-Pad2)") (class "Default")
      (node (ref "C153") (pin "2") (pinfunction "2_2") (pintype "passive"))
      (node (ref "L31") (pin "2") (pinfunction "2_2") (pintype "passive"))
      (node (ref "L32") (pin "1") (pinfunction "1_1") (pintype "passive"))
    )
    (net (code "27") (name "Net-(C154-Pad2)") (class "Default")
      (node (ref "C154") (pin "2") (pinfunction "2_2") (pintype "passive"))
      (node (ref "C155") (pin "2") (pinfunction "2_2") (pintype "passive"))
      (node (ref "L32") (pin "2") (pinfunction "2_2") (pintype "passive"))
      (node (ref "R70") (pin "2") (pinfunction "2_2") (pintype "passive"))
    )
    (net (code "28") (name "Net-(C165-Pad2)") (class "Default")
      (node (ref "C165") (pin "2") (pinfunction "2_2") (pintype "passive"))
      (node (ref "R74") (pin "2") (pinfunction "2_2") (pintype "passive"))
    )
    (net (code "29") (name "Net-(D21A-D0)") (class "Default")
      (node (ref "D21") (pin "48") (pinfunction "D0_48") (pintype "input"))
      (node (ref "R50") (pin "5") (pinfunction "5_5") (pintype "passive"))
    )
    (net (code "30") (name "Net-(D21A-D1)") (class "Default")
      (node (ref "D21") (pin "44") (pinfunction "D1_44") (pintype "input"))
      (node (ref "R50") (pin "6") (pinfunction "6_6") (pintype "passive"))
    )
    (net (code "31") (name "Net-(D21A-D2)") (class "Default")
      (node (ref "D21") (pin "43") (pinfunction "D2_43") (pintype "input"))
      (node (ref "R50") (pin "7") (pinfunction "7_7") (pintype "passive"))
    )
    (net (code "32") (name "Net-(D21A-D3)") (class "Default")
      (node (ref "D21") (pin "42") (pinfunction "D3_42") (pintype "input"))
      (node (ref "R50") (pin "8") (pinfunction "8_8") (pintype "passive"))
    )
    (net (code "33") (name "Net-(D21A-D4)") (class "Default")
      (node (ref "D21") (pin "39") (pinfunction "D4_39") (pintype "input"))
      (node (ref "R53") (pin "5") (pinfunction "5_5") (pintype "passive"))
    )
    (net (code "34") (name "Net-(D21A-D5)") (class "Default")
      (node (ref "D21") (pin "38") (pinfunction "D5_38") (pintype "input"))
      (node (ref "R53") (pin "6") (pinfunction "6_6") (pintype "passive"))
    )
    (net (code "35") (name "Net-(D21A-D6)") (class "Default")
      (node (ref "D21") (pin "37") (pinfunction "D6_37") (pintype "input"))
      (node (ref "R53") (pin "7") (pinfunction "7_7") (pintype "passive"))
    )
    (net (code "36") (name "Net-(D21A-D7)") (class "Default")
      (node (ref "D21") (pin "36") (pinfunction "D7_36") (pintype "input"))
      (node (ref "R53") (pin "8") (pinfunction "8_8") (pintype "passive"))
    )
    (net (code "37") (name "Net-(D21A-D8)") (class "Default")
      (node (ref "D21") (pin "35") (pinfunction "D8_35") (pintype "input"))
      (node (ref "R56") (pin "5") (pinfunction "5_5") (pintype "passive"))
    )
    (net (code "38") (name "Net-(D21A-D9)") (class "Default")
      (node (ref "D21") (pin "34") (pinfunction "D9_34") (pintype "input"))
      (node (ref "R56") (pin "6") (pinfunction "6_6") (pintype "passive"))
    )
    (net (code "39") (name "Net-(D21A-D10)") (class "Default")
      (node (ref "D21") (pin "33") (pinfunction "D10_33") (pintype "input"))
      (node (ref "R56") (pin "7") (pinfunction "7_7") (pintype "passive"))
    )
    (net (code "40") (name "Net-(D21A-D11)") (class "Default")
      (node (ref "D21") (pin "32") (pinfunction "D11_32") (pintype "input"))
      (node (ref "R56") (pin "8") (pinfunction "8_8") (pintype "passive"))
    )
    (net (code "41") (name "Net-(D21A-D12)") (class "Default")
      (node (ref "D21") (pin "31") (pinfunction "D12_31") (pintype "input"))
      (node (ref "R57") (pin "5") (pinfunction "5_5") (pintype "passive"))
    )
    (net (code "42") (name "Net-(D21A-D13)") (class "Default")
      (node (ref "D21") (pin "27") (pinfunction "D13_27") (pintype "input"))
      (node (ref "R57") (pin "6") (pinfunction "6_6") (pintype "passive"))
    )
    (net (code "43") (name "Net-(D21A-D14)") (class "Default")
      (node (ref "D21") (pin "26") (pinfunction "D14_26") (pintype "input"))
      (node (ref "R57") (pin "7") (pinfunction "7_7") (pintype "passive"))
    )
    (net (code "44") (name "Net-(D21A-D15)") (class "Default")
      (node (ref "D21") (pin "25") (pinfunction "D15_25") (pintype "input"))
      (node (ref "R57") (pin "8") (pinfunction "8_8") (pintype "passive"))
    )
    (net (code "45") (name "Net-(D21A-DAC_RSET)") (class "Default")
      (node (ref "D21") (pin "84") (pinfunction "DAC_RSET_84") (pintype "input"))
      (node (ref "R51") (pin "2") (pinfunction "2_2") (pintype "passive"))
    )
    (net (code "46") (name "Net-(D21A-F0)") (class "Default")
      (node (ref "D21") (pin "50") (pinfunction "F0_50") (pintype "input"))
      (node (ref "R60") (pin "6") (pinfunction "6_6") (pintype "passive"))
    )
    (net (code "47") (name "Net-(D21A-F1)") (class "Default")
      (node (ref "D21") (pin "49") (pinfunction "F1_49") (pintype "input"))
      (node (ref "R60") (pin "7") (pinfunction "7_7") (pintype "passive"))
    )
    (net (code "48") (name "Net-(D22A-CMA)") (class "Default")
      (node (ref "C161") (pin "2") (pinfunction "2_2") (pintype "passive"))
      (node (ref "D22") (pin "24") (pinfunction "TB_24") (pintype "passive"))
      (node (ref "D22") (pin "26") (pinfunction "CMC_26") (pintype "input"))
      (node (ref "D22") (pin "27") (pinfunction "CMB_27") (pintype "input"))
      (node (ref "D22") (pin "28") (pinfunction "CMA_28") (pintype "input"))
    )
    (net (code "49") (name "Net-(D22A-OUT0+)") (class "Default")
      (node (ref "C156") (pin "2") (pinfunction "2_2") (pintype "passive"))
      (node (ref "D22") (pin "9") (pinfunction "OUT0+_9") (pintype "passive"))
    )
    (net (code "50") (name "Net-(D22A-OUT0-)") (class "Default")
      (node (ref "C157") (pin "2") (pinfunction "2_2") (pintype "passive"))
      (node (ref "D22") (pin "8") (pinfunction "OUT0-_8") (pintype "passive"))
    )
    (net (code "51") (name "Net-(D22A-OUT2+)") (class "Default")
      (node (ref "C158") (pin "2") (pinfunction "2_2") (pintype "passive"))
      (node (ref "D22") (pin "3") (pinfunction "OUT2+_3") (pintype "passive"))
    )
    (net (code "52") (name "Net-(D22A-OUT2-)") (class "Default")
      (node (ref "C159") (pin "2") (pinfunction "2_2") (pintype "passive"))
      (node (ref "D22") (pin "2") (pinfunction "OUT2-_2") (pintype "passive"))
    )
    (net (code "53") (name "Net-(D22A-OUT3+)") (class "Default")
      (node (ref "C160") (pin "2") (pinfunction "2_2") (pintype "passive"))
      (node (ref "D22") (pin "12") (pinfunction "OUT3+_12") (pintype "passive"))
    )
    (net (code "54") (name "Net-(D22A-OUT3-)") (class "Default")
      (node (ref "C162") (pin "2") (pinfunction "2_2") (pintype "passive"))
      (node (ref "D22") (pin "11") (pinfunction "OUT3-_11") (pintype "passive"))
    )
    (net (code "55") (name "Net-(D22B-BB)") (class "Default")
      (node (ref "C188") (pin "1") (pinfunction "1_1") (pintype "passive"))
      (node (ref "D22") (pin "22") (pinfunction "BB_22") (pintype "input"))
    )
    (net (code "56") (name "Net-(D22B-BVCO)") (class "Default")
      (node (ref "C184") (pin "2") (pinfunction "2_2") (pintype "passive"))
      (node (ref "D22") (pin "30") (pinfunction "BVCO_30") (pintype "passive"))
    )
    (net (code "57") (name "Net-(D22B-VCP+)") (class "Default")
      (node (ref "C174") (pin "2") (pinfunction "2_2") (pintype "passive"))
      (node (ref "C175") (pin "2") (pinfunction "2_2") (pintype "passive"))
      (node (ref "D22") (pin "33") (pinfunction "VCP+_33") (pintype "power_in"))
      (node (ref "R75") (pin "1") (pinfunction "1_1") (pintype "passive"))
    )
    (net (code "58") (name "Net-(D23A-RFC)") (class "Default")
      (node (ref "D23") (pin "7") (pinfunction "RFC_7") (pintype "passive"))
      (node (ref "T7") (pin "6") (pinfunction "6_6") (pintype "passive"))
    )
    (net (code "59") (name "Net-(H4-K)") (class "Default")
      (node (ref "H4") (pin "1") (pinfunction "K_1") (pintype "passive"))
      (node (ref "R54") (pin "1") (pinfunction "1_1") (pintype "passive"))
    )
    (net (code "60") (name "Net-(L33-Pad1)") (class "Default")
      (node (ref "L33") (pin "1") (pinfunction "1_1") (pintype "passive"))
      (node (ref "R73") (pin "1") (pinfunction "1_1") (pintype "passive"))
    )
    (net (code "61") (name "Net-(Q1-OUT)") (class "Default")
      (node (ref "Q1") (pin "3") (pinfunction "OUT_3") (pintype "output"))
      (node (ref "R61") (pin "2") (pinfunction "2_2") (pintype "passive"))
      (node (ref "R62") (pin "1") (pinfunction "1_1") (pintype "passive"))
    )
    (net (code "62") (name "Net-(Q1-VDD)") (class "Default")
      (node (ref "C145") (pin "2") (pinfunction "2_2") (pintype "passive"))
      (node (ref "C146") (pin "2") (pinfunction "2_2") (pintype "passive"))
      (node (ref "Q1") (pin "4") (pinfunction "VDD_4") (pintype "passive"))
      (node (ref "R59") (pin "1") (pinfunction "1_1") (pintype "passive"))
    )
    (net (code "63") (name "Net-(R64-Pad2)") (class "Default")
      (node (ref "R64") (pin "2") (pinfunction "2_2") (pintype "passive"))
      (node (ref "R69") (pin "1") (pinfunction "1_1") (pintype "passive"))
      (node (ref "R70") (pin "1") (pinfunction "1_1") (pintype "passive"))
    )
    (net (code "64") (name "Net-(R65-Pad2)") (class "Default")
      (node (ref "R65") (pin "2") (pinfunction "2_2") (pintype "passive"))
      (node (ref "R66") (pin "2") (pinfunction "2_2") (pintype "passive"))
      (node (ref "R68") (pin "1") (pinfunction "1_1") (pintype "passive"))
    )
    (net (code "65") (name "Net-(T6-D)") (class "Default")
      (node (ref "R54") (pin "2") (pinfunction "2_2") (pintype "passive"))
      (node (ref "T6") (pin "3") (pinfunction "D_3") (pintype "passive"))
    )
    (net (code "66") (name "Net-(XW2-RF)") (class "Default")
      (node (ref "C144") (pin "2") (pinfunction "2_2") (pintype "passive"))
      (node (ref "XW2") (pin "S") (pinfunction "RF_S") (pintype "passive"))
    )
    (net (code "67") (name "SCLK_LTC6951") (class "Default")
      (node (ref "D22") (pin "18") (pinfunction "SCLK_18") (pintype "input"))
    )
    (net (code "68") (name "STAT_LTC6951") (class "Default")
      (node (ref "D22") (pin "38") (pinfunction "STAT_38") (pintype "passive"))
    )
    (net (code "69") (name "SYNC_LTC6951") (class "Default")
      (node (ref "D22") (pin "39") (pinfunction "SYNC_39") (pintype "input"))
      (node (ref "R76") (pin "2") (pinfunction "2_2") (pintype "passive"))
    )
    (net (code "70") (name "_3V3") (class "Default")
      (node (ref "H4") (pin "2") (pinfunction "A_2") (pintype "passive"))
    )
    (net (code "71") (name "_3V3_flt") (class "Default")
      (node (ref "C185") (pin "1") (pinfunction "1_1") (pintype "passive"))
      (node (ref "D23") (pin "16") (pinfunction "VDD_16") (pintype "passive"))
    )
    (net (code "72") (name "_DDS_SYNC_CLK") (class "Default")
      (node (ref "D21") (pin "55") (pinfunction "SYNC_CLK_55") (pintype "output"))
    )
    (net (code "73") (name "_cpld_clk") (class "Default")
      (node (ref "R52") (pin "1") (pinfunction "1_1") (pintype "passive"))
      (node (ref "R55") (pin "2") (pinfunction "2_2") (pintype "passive"))
      (node (ref "T5") (pin "6") (pinfunction "6_6") (pintype "passive"))
    )
    (net (code "74") (name "_ext_ref_n") (class "Default")
      (node (ref "D22") (pin "37") (pinfunction "REF+_37") (pintype "passive"))
      (node (ref "R72") (pin "2") (pinfunction "2_2") (pintype "passive"))
      (node (ref "T7") (pin "3") (pinfunction "3_3") (pintype "passive"))
    )
    (net (code "75") (name "_ext_ref_p") (class "Default")
      (node (ref "D22") (pin "36") (pinfunction "REF-_36") (pintype "passive"))
      (node (ref "R72") (pin "1") (pinfunction "1_1") (pintype "passive"))
      (node (ref "T7") (pin "1") (pinfunction "1_1") (pintype "passive"))
    )
    (net (code "76") (name "_int_ref") (class "Default")
      (node (ref "C147") (pin "1") (pinfunction "1_1") (pintype "passive"))
      (node (ref "D23") (pin "11") (pinfunction "RF2_11") (pintype "passive"))
    )
    (net (code "77") (name "_iout_dds_n") (class "Default")
      (node (ref "C152") (pin "2") (pinfunction "2_2") (pintype "passive"))
      (node (ref "D21") (pin "80") (pinfunction "~{IOUT}_80") (pintype "output"))
      (node (ref "L31") (pin "1") (pinfunction "1_1") (pintype "passive"))
      (node (ref "R68") (pin "2") (pinfunction "2_2") (pintype "passive"))
    )
    (net (code "78") (name "_iout_dds_p") (class "Default")
      (node (ref "C149") (pin "1") (pinfunction "1_1") (pintype "passive"))
      (node (ref "D21") (pin "81") (pinfunction "IOUT_81") (pintype "output"))
      (node (ref "L29") (pin "1") (pinfunction "1_1") (pintype "passive"))
      (node (ref "R65") (pin "1") (pinfunction "1_1") (pintype "passive"))
    )
    (net (code "79") (name "_lo1_ref_n") (class "Default")
      (node (ref "C162") (pin "1") (pinfunction "1_1") (pintype "passive"))
    )
    (net (code "80") (name "_lo1_ref_p") (class "Default")
      (node (ref "C160") (pin "1") (pinfunction "1_1") (pintype "passive"))
    )
    (net (code "81") (name "_lo2_cp") (class "Default")
      (node (ref "C164") (pin "2") (pinfunction "2_2") (pintype "passive"))
      (node (ref "D22") (pin "34") (pinfunction "CP_34") (pintype "passive"))
      (node (ref "L33") (pin "2") (pinfunction "2_2") (pintype "passive"))
    )
    (net (code "82") (name "_lo2_vtune") (class "Default")
      (node (ref "C163") (pin "2") (pinfunction "2_2") (pintype "passive"))
      (node (ref "D22") (pin "23") (pinfunction "TUNE_23") (pintype "input"))
      (node (ref "R73") (pin "2") (pinfunction "2_2") (pintype "passive"))
      (node (ref "R74") (pin "1") (pinfunction "1_1") (pintype "passive"))
    )
    (net (code "83") (name "cpld_clk_n") (class "Default")
      (node (ref "D22") (pin "14") (pinfunction "OUT4-_14") (pintype "passive"))
      (node (ref "T5") (pin "3") (pinfunction "3_3") (pintype "passive"))
    )
    (net (code "84") (name "cpld_clk_p") (class "Default")
      (node (ref "D22") (pin "15") (pinfunction "OUT4+_15") (pintype "passive"))
      (node (ref "T5") (pin "1") (pinfunction "1_1") (pintype "passive"))
    )
    (net (code "85") (name "dds_cs") (class "Default")
      (node (ref "D21") (pin "70") (pinfunction "~{CS}_70") (pintype "input"))
    )
    (net (code "86") (name "dds_d00") (class "Default")
      (node (ref "R50") (pin "4") (pinfunction "4_4") (pintype "passive"))
    )
    (net (code "87") (name "dds_d01") (class "Default")
      (node (ref "R50") (pin "3") (pinfunction "3_3") (pintype "passive"))
    )
    (net (code "88") (name "dds_d02") (class "Default")
      (node (ref "R50") (pin "2") (pinfunction "2_2") (pintype "passive"))
    )
    (net (code "89") (name "dds_d03") (class "Default")
      (node (ref "R50") (pin "1") (pinfunction "1_1") (pintype "passive"))
    )
    (net (code "90") (name "dds_d04") (class "Default")
      (node (ref "R53") (pin "4") (pinfunction "4_4") (pintype "passive"))
    )
    (net (code "91") (name "dds_d05") (class "Default")
      (node (ref "R53") (pin "3") (pinfunction "3_3") (pintype "passive"))
    )
    (net (code "92") (name "dds_d06") (class "Default")
      (node (ref "R53") (pin "2") (pinfunction "2_2") (pintype "passive"))
    )
    (net (code "93") (name "dds_d07") (class "Default")
      (node (ref "R53") (pin "1") (pinfunction "1_1") (pintype "passive"))
    )
    (net (code "94") (name "dds_d08") (class "Default")
      (node (ref "R56") (pin "4") (pinfunction "4_4") (pintype "passive"))
    )
    (net (code "95") (name "dds_d09") (class "Default")
      (node (ref "R56") (pin "3") (pinfunction "3_3") (pintype "passive"))
    )
    (net (code "96") (name "dds_d10") (class "Default")
      (node (ref "R56") (pin "2") (pinfunction "2_2") (pintype "passive"))
    )
    (net (code "97") (name "dds_d11") (class "Default")
      (node (ref "R56") (pin "1") (pinfunction "1_1") (pintype "passive"))
    )
    (net (code "98") (name "dds_d12") (class "Default")
      (node (ref "R57") (pin "4") (pinfunction "4_4") (pintype "passive"))
    )
    (net (code "99") (name "dds_d13") (class "Default")
      (node (ref "R57") (pin "3") (pinfunction "3_3") (pintype "passive"))
    )
    (net (code "100") (name "dds_d14") (class "Default")
      (node (ref "R57") (pin "2") (pinfunction "2_2") (pintype "passive"))
    )
    (net (code "101") (name "dds_d15") (class "Default")
      (node (ref "R57") (pin "1") (pinfunction "1_1") (pintype "passive"))
    )
    (net (code "102") (name "dds_f0") (class "Default")
      (node (ref "R60") (pin "3") (pinfunction "3_3") (pintype "passive"))
    )
    (net (code "103") (name "dds_f1") (class "Default")
      (node (ref "R60") (pin "2") (pinfunction "2_2") (pintype "passive"))
    )
    (net (code "104") (name "dds_io_reset") (class "Default")
      (node (ref "D21") (pin "71") (pinfunction "I/O_RESET_71") (pintype "input"))
    )
    (net (code "105") (name "dds_io_update") (class "Default")
      (node (ref "D21") (pin "59") (pinfunction "I/O_UPDATE_59") (pintype "bidirectional"))
    )
    (net (code "106") (name "dds_master_reset") (class "Default")
      (node (ref "D21") (pin "14") (pinfunction "MASTER_RESET_14") (pintype "input"))
    )
    (net (code "107") (name "dds_pdclk") (class "Default")
      (node (ref "D21") (pin "40") (pinfunction "PDCLK_40") (pintype "output"))
    )
    (net (code "108") (name "dds_profile0") (class "Default")
      (node (ref "D21") (pin "54") (pinfunction "PROFILE0_54") (pintype "input"))
    )
    (net (code "109") (name "dds_profile1") (class "Default")
      (node (ref "D21") (pin "53") (pinfunction "PROFILE1_53") (pintype "input"))
    )
    (net (code "110") (name "dds_profile2") (class "Default")
      (node (ref "D21") (pin "52") (pinfunction "PROFILE2_52") (pintype "input"))
    )
    (net (code "111") (name "dds_sclk") (class "Default")
      (node (ref "D21") (pin "69") (pinfunction "SCLK_69") (pintype "input"))
    )
    (net (code "112") (name "dds_sdio") (class "Default")
      (node (ref "D21") (pin "67") (pinfunction "SDIO_67") (pintype "bidirectional"))
    )
    (net (code "113") (name "dds_sdo") (class "Default")
      (node (ref "D21") (pin "68") (pinfunction "SDO_68") (pintype "output"))
    )
    (net (code "114") (name "dds_sync_n") (class "Default")
      (node (ref "D21") (pin "8") (pinfunction "SYNC_IN-_8") (pintype "input"))
    )
    (net (code "115") (name "dds_sync_p") (class "Default")
      (node (ref "D21") (pin "7") (pinfunction "SYNC_IN+_7") (pintype "input"))
    )
    (net (code "116") (name "dds_sync_smp_err") (class "Default")
      (node (ref "D21") (pin "12") (pinfunction "SYNC_SMP_ERR_12") (pintype "output"))
    )
    (net (code "117") (name "dds_txenable") (class "Default")
      (node (ref "D21") (pin "41") (pinfunction "TXENABLE_41") (pintype "input"))
    )
    (net (code "118") (name "ram_swp_ovr") (class "Default")
      (node (ref "D21") (pin "24") (pinfunction "RAM_SWP_OVR_24") (pintype "output"))
    )
    (net (code "119") (name "ref_freq_rx_n") (class "Default")
      (node (ref "C156") (pin "1") (pinfunction "1_1") (pintype "passive"))
    )
    (net (code "120") (name "ref_freq_rx_p") (class "Default")
      (node (ref "C157") (pin "1") (pinfunction "1_1") (pintype "passive"))
    )
    (net (code "121") (name "unconnected-(D21A-DROVER-Pad61)") (class "Default")
      (node (ref "D21") (pin "61") (pinfunction "DROVER_61") (pintype "output+no_connect"))
    )
    (net (code "122") (name "unconnected-(D21A-LOOP_FILTER-Pad2)") (class "Default")
      (node (ref "D21") (pin "2") (pinfunction "LOOP_FILTER_2") (pintype "passive+no_connect"))
    )
    (net (code "123") (name "unconnected-(D21A-NC-Pad1)") (class "Default")
      (node (ref "D21") (pin "1") (pinfunction "NC_1") (pintype "passive+no_connect"))
    )
    (net (code "124") (name "unconnected-(D21A-NC-Pad20)") (class "Default")
      (node (ref "D21") (pin "20") (pinfunction "NC_20") (pintype "passive+no_connect"))
    )
    (net (code "125") (name "unconnected-(D21A-NC-Pad72)") (class "Default")
      (node (ref "D21") (pin "72") (pinfunction "NC_72") (pintype "passive+no_connect"))
    )
    (net (code "126") (name "unconnected-(D21A-NC-Pad86)") (class "Default")
      (node (ref "D21") (pin "86") (pinfunction "NC_86") (pintype "passive+no_connect"))
    )
    (net (code "127") (name "unconnected-(D21A-NC-Pad87)") (class "Default")
      (node (ref "D21") (pin "87") (pinfunction "NC_87") (pintype "passive+no_connect"))
    )
    (net (code "128") (name "unconnected-(D21A-NC-Pad93)") (class "Default")
      (node (ref "D21") (pin "93") (pinfunction "NC_93") (pintype "passive+no_connect"))
    )
    (net (code "129") (name "unconnected-(D21A-NC-Pad97)") (class "Default")
      (node (ref "D21") (pin "97") (pinfunction "NC_97") (pintype "passive+no_connect"))
    )
    (net (code "130") (name "unconnected-(D21A-NC-Pad98)") (class "Default")
      (node (ref "D21") (pin "98") (pinfunction "NC_98") (pintype "passive+no_connect"))
    )
    (net (code "131") (name "unconnected-(D21A-NC-Pad99)") (class "Default")
      (node (ref "D21") (pin "99") (pinfunction "NC_99") (pintype "passive+no_connect"))
    )
    (net (code "132") (name "unconnected-(D21A-NC-Pad100)") (class "Default")
      (node (ref "D21") (pin "100") (pinfunction "NC_100") (pintype "passive+no_connect"))
    )
    (net (code "133") (name "unconnected-(D21A-PLL_LOCK-Pad19)") (class "Default")
      (node (ref "D21") (pin "19") (pinfunction "PLL_LOCK_19") (pintype "output+no_connect"))
    )
    (net (code "134") (name "unconnected-(D21A-REFCLK_OUT-Pad94)") (class "Default")
      (node (ref "D21") (pin "94") (pinfunction "REFCLK_OUT_94") (pintype "output+no_connect"))
    )
    (net (code "135") (name "unconnected-(D21A-SYNC_OUT+-Pad9)") (class "Default")
      (node (ref "D21") (pin "9") (pinfunction "SYNC_OUT+_9") (pintype "output+no_connect"))
    )
    (net (code "136") (name "unconnected-(D21A-SYNC_OUT--Pad10)") (class "Default")
      (node (ref "D21") (pin "10") (pinfunction "SYNC_OUT-_10") (pintype "output+no_connect"))
    )
    (net (code "137") (name "unconnected-(D22A-OUT1+-Pad6)") (class "Default")
      (node (ref "D22") (pin "6") (pinfunction "OUT1+_6") (pintype "passive+no_connect"))
    )
    (net (code "138") (name "unconnected-(D22A-OUT1--Pad5)") (class "Default")
      (node (ref "D22") (pin "5") (pinfunction "OUT1-_5") (pintype "passive+no_connect"))
    )
    (net (code "139") (name "unconnected-(Q1-NC-Pad1)") (class "Default")
      (node (ref "Q1") (pin "1") (pinfunction "NC_1") (pintype "passive+no_connect"))
    )
    (net (code "140") (name "unconnected-(R60-Pad1)") (class "Default")
      (node (ref "R60") (pin "1") (pinfunction "1_1") (pintype "passive"))
    )
    (net (code "141") (name "unconnected-(R60-Pad4)") (class "Default")
      (node (ref "R60") (pin "4") (pinfunction "4_4") (pintype "passive"))
    )
    (net (code "142") (name "unconnected-(R60-Pad5)") (class "Default")
      (node (ref "R60") (pin "5") (pinfunction "5_5") (pintype "passive"))
    )
    (net (code "143") (name "unconnected-(R60-Pad8)") (class "Default")
      (node (ref "R60") (pin "8") (pinfunction "8_8") (pintype "passive"))
    )
    (net (code "144") (name "unconnected-(T5-Pad2)") (class "Default")
      (node (ref "T5") (pin "2") (pinfunction "2_2") (pintype "passive+no_connect"))
    )
    (net (code "145") (name "unconnected-(T7-Pad2)") (class "Default")
      (node (ref "T7") (pin "2") (pinfunction "2_2") (pintype "passive+no_connect"))
    )
  )
)
